# Fly-Back.net
KiCad netlist of a schematic drawn in Altium Designer
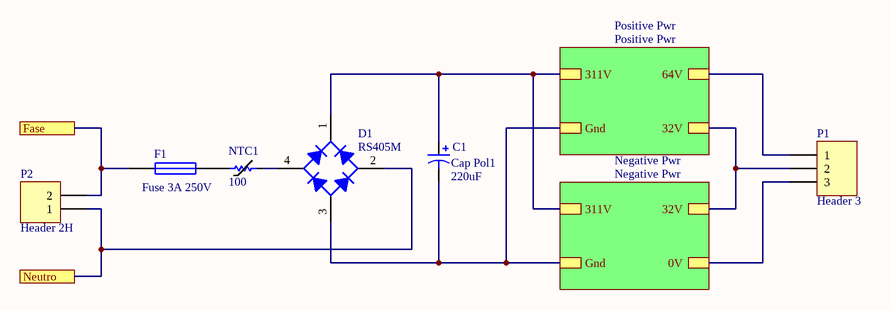
[diagram p0: Fly-Back.SchDoc]

(export (version "E")
  (design (tool "Eeschema 10.0.6"))
  (components
    (comp (ref "C1")
      (value "Cap Pol1")
      (footprint "cap rad 100mm")
      (description "Polarized Capacitor (Radial)")
      (fields (field (name "ALTIUM_VALUE") "220uF") (field (name "PUBLISHER") "Altium Limited"))
      (libsource (lib "Miscellaneous Devices") (part "Cap Pol1"))
    )
    (comp (ref "D1")
      (value "RS405M")
      (footprint "RS405M")
      (description "Full Wave Diode Bridge")
      (fields (field (name "PUBLISHER") "Altium Limited"))
      (libsource (lib "Miscellaneous Devices") (part "Bridge1"))
    )
    (comp (ref "F1")
      (value "Fuse 3A 250V")
      (footprint "FUSE 3A")
      (description "Fuse")
      (fields (field (name "PUBLISHER") "Altium Limited"))
      (libsource (lib "Miscellaneous Devices") (part "Fuse 1"))
    )
    (comp (ref "NTC1")
      (value "Termistor NTC")
      (footprint "RAD-0.3")
      (description "Termistor NTC SMD")
      (fields (field (name "VALOR") "100"))
      (libsource (lib "RUF-Dispositivos-Grales") (part "Termistor NTC"))
    )
    (comp (ref "P1")
      (value "Header 3")
      (footprint "bornera 3")
      (description "Header, 3-Pin")
      (fields (field (name "PUBLISHER") "Altium Limited"))
      (libsource (lib "Miscellaneous Connectors") (part "Header 3"))
    )
    (comp (ref "P2")
      (value "Header 2H")
      (footprint "bornera 2")
      (description "Header, 2-Pin, Right Angle")
      (fields (field (name "PUBLISHER") "Altium Limited"))
      (libsource (lib "Miscellaneous Connectors") (part "Header 2H"))
    )
  )
  (nets
    (net (code "1") (name "/0V") (class "Default")
      (node (ref "P1") (pin "3") (pinfunction "3_3") (pintype "passive"))
    )
    (net (code "2") (name "/32V") (class "Default")
      (node (ref "P1") (pin "2") (pinfunction "2_2") (pintype "passive"))
    )
    (net (code "3") (name "/64V") (class "Default")
      (node (ref "P1") (pin "1") (pinfunction "1_1") (pintype "passive"))
    )
    (net (code "4") (name "/311V") (class "Default")
      (node (ref "C1") (pin "1") (pinfunction "1_1") (pintype "passive"))
      (node (ref "D1") (pin "1") (pinfunction "K_1") (pintype "passive"))
    )
    (net (code "5") (name "/Fase") (class "Default")
      (node (ref "F1") (pin "1") (pinfunction "1_1") (pintype "passive"))
      (node (ref "P2") (pin "2") (pinfunction "2_2") (pintype "passive"))
    )
    (net (code "6") (name "/Gnd") (class "Default")
      (node (ref "C1") (pin "2") (pinfunction "2_2") (pintype "passive"))
      (node (ref "D1") (pin "3") (pinfunction "A_3") (pintype "passive"))
    )
    (net (code "7") (name "/Neutro") (class "Default")
      (node (ref "D1") (pin "2") (pinfunction "C_2") (pintype "passive"))
      (node (ref "P2") (pin "1") (pinfunction "1_1") (pintype "passive"))
    )
    (net (code "8") (name "Net-(D1-C-Pad4)") (class "Default")
      (node (ref "D1") (pin "4") (pinfunction "C_4") (pintype "passive"))
      (node (ref "NTC1") (pin "1") (pinfunction "1_1") (pintype "passive"))
    )
    (net (code "9") (name "Net-(F1-Pad2)") (class "Default")
      (node (ref "F1") (pin "2") (pinfunction "2_2") (pintype "passive"))
      (node (ref "NTC1") (pin "2") (pinfunction "2_2") (pintype "passive"))
    )
  )
)
